# MCU.net
KiCad netlist of a schematic drawn in Altium Designer
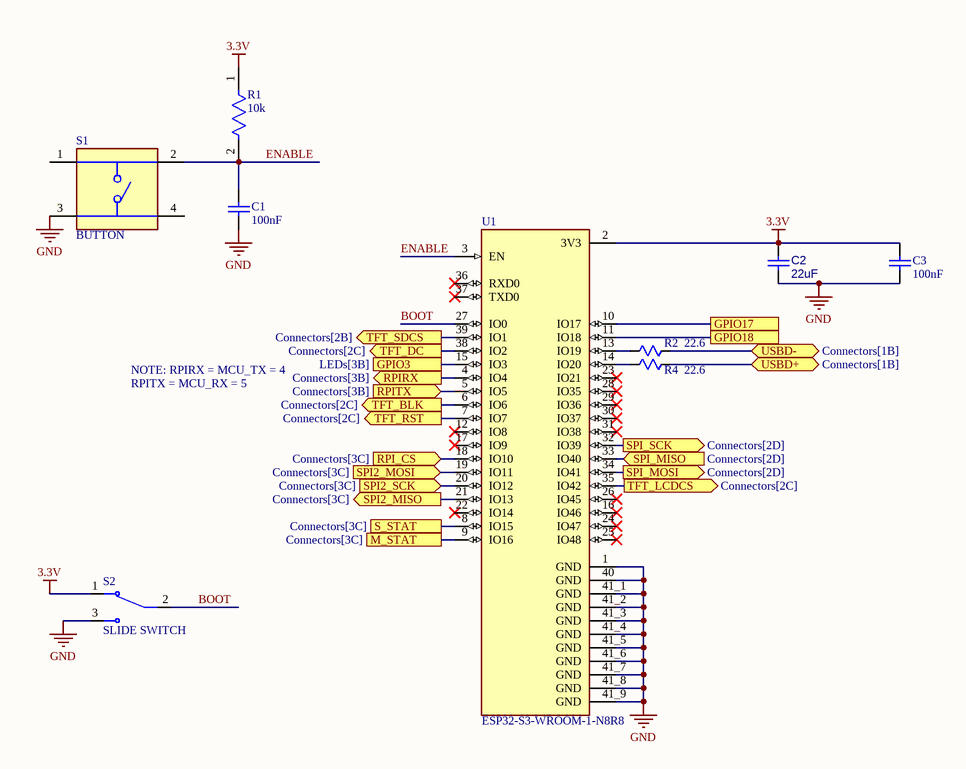
[diagram p0: MCU.SchDoc]

(export (version "E")
  (design (tool "Eeschema 10.0.6"))
  (components
    (comp (ref "C1")
      (value "100nF")
      (footprint "CAPC1608X90X35LL10T15")
      (fields (field (name "PART NUMBER") "GRM188R71E104KA01D") (field (name "MANUFACTURER") "Murata"))
      (libsource (lib "Altium Content Vault") (part "CAP"))
    )
    (comp (ref "C2")
      (value "22uF")
      (footprint "CAPC1608X09N")
      (description "CAP CER 22uF 10V X5R Symbols/Capacitor-Generic.SchLib")
      (fields (field (name "VOLTAGE") "10V") (field (name "PART NUMBER") "CAP-0603-000010"))
      (libsource (lib "Satellite Team") (part "CAP-NP-1"))
    )
    (comp (ref "C3")
      (value "100nF")
      (footprint "CAPC1608X90X35LL10T15")
      (fields (field (name "PART NUMBER") "GRM188R71E104KA01D") (field (name "MANUFACTURER") "Murata"))
      (libsource (lib "Altium Content Vault") (part "CAP"))
    )
    (comp (ref "R1")
      (value "10k")
      (footprint "FP-CRGP0603-IPC_C")
      (description "CRGP 0603 10K 1%")
      (fields
        (field (name "OCTOPART") "https://octopart.com/crgp0603f10k-te+connectivity-91018721")
        (field (name "MANUFACTURER PART NUMBER") "CRGP0603F10K")
      )
      (libsource (lib "Altium Content Vault") (part "1029c3af85768c4190bb7ad29bc67b5"))
    )
    (comp (ref "R2")
      (value "22.6")
      (footprint "RESC1608X06N")
      (description "RES 22.6 OHM 1% 1/10W 0603")
      (fields (field (name "PART NUMBER") "RES-0603-22R6-001") (field (name "TOLERANCE") "0.01%"))
      (libsource (lib "Satellite Team") (part "RES-1"))
    )
    (comp (ref "R4")
      (value "22.6")
      (footprint "RESC1608X06N")
      (description "RES 22.6 OHM 1% 1/10W 0603")
      (fields (field (name "PART NUMBER") "RES-0603-22R6-001") (field (name "TOLERANCE") "0.01%"))
      (libsource (lib "Satellite Team") (part "RES-1"))
    )
    (comp (ref "S1")
      (value "BUTTON")
      (footprint "SW_TS02-66-43-BK-100-SCR-D")
      (description "Switch Tactile OFF (ON) SPST Round Button PC Pins 0.05A 12VDC 100000Cycles 1N Thru-Hole Bag")
      (libsource (lib "Satellite Team") (part "TS02-66-43-BK-100-SCR-D"))
    )
    (comp (ref "S2")
      (value "SLIDE SWITCH")
      (footprint "SW_SLW-883935-2A-D")
      (description "Switch Slide ON ON SPDT Raised Slide 0.5A 30VDC 10000Cycles PC Pins Thru-Hole Box")
      (libsource (lib "Satellite Team") (part "SLW-883935-2A-D"))
    )
    (comp (ref "U1")
      (value "ESP32-S3-WROOM-1-N8R8")
      (footprint "XCVR_ESP32S3WROOM1N8R8")
      (description "Bluetooth, WiFi 802.11b/g/n, Bluetooth v5.0 Transceiver Module 2.4GHz PCB Trace Surface Mount")
      (fields (field (name "MF") "Espressif Systems"))
      (libsource (lib "ESP32-S3-WROOM-1-N8R8") (part "ESP32-S3-WROOM-1-N8R8"))
    )
  )
  (nets
    (net (code "1") (name "/BOOT") (class "Default")
      (node (ref "S2") (pin "2") (pinfunction "2_2") (pintype "passive"))
      (node (ref "U1") (pin "27") (pinfunction "IO0_27") (pintype "bidirectional"))
    )
    (net (code "2") (name "/ENABLE") (class "Default")
      (node (ref "C1") (pin "2") (pinfunction "2_2") (pintype "passive"))
      (node (ref "R1") (pin "2") (pinfunction "2_2") (pintype "passive"))
      (node (ref "S1") (pin "2") (pinfunction "2_2") (pintype "passive"))
      (node (ref "U1") (pin "3") (pinfunction "EN_3") (pintype "input"))
    )
    (net (code "3") (name "/GPIO3") (class "Default")
      (node (ref "U1") (pin "15") (pinfunction "IO3_15") (pintype "bidirectional"))
    )
    (net (code "4") (name "/GPIO17") (class "Default")
      (node (ref "U1") (pin "10") (pinfunction "IO17_10") (pintype "bidirectional"))
    )
    (net (code "5") (name "/GPIO18") (class "Default")
      (node (ref "U1") (pin "11") (pinfunction "IO18_11") (pintype "bidirectional"))
    )
    (net (code "6") (name "/M_STAT") (class "Default")
      (node (ref "U1") (pin "9") (pinfunction "IO16_9") (pintype "bidirectional"))
    )
    (net (code "7") (name "/RPIRX") (class "Default")
      (node (ref "U1") (pin "4") (pinfunction "IO4_4") (pintype "bidirectional"))
    )
    (net (code "8") (name "/RPITX") (class "Default")
      (node (ref "U1") (pin "5") (pinfunction "IO5_5") (pintype "bidirectional"))
    )
    (net (code "9") (name "/RPI_CS") (class "Default")
      (node (ref "U1") (pin "18") (pinfunction "IO10_18") (pintype "bidirectional"))
    )
    (net (code "10") (name "/SPI2_MISO") (class "Default")
      (node (ref "U1") (pin "21") (pinfunction "IO13_21") (pintype "bidirectional"))
    )
    (net (code "11") (name "/SPI2_MOSI") (class "Default")
      (node (ref "U1") (pin "19") (pinfunction "IO11_19") (pintype "bidirectional"))
    )
    (net (code "12") (name "/SPI2_SCK") (class "Default")
      (node (ref "U1") (pin "20") (pinfunction "IO12_20") (pintype "bidirectional"))
    )
    (net (code "13") (name "/SPI_MISO") (class "Default")
      (node (ref "U1") (pin "33") (pinfunction "IO40_33") (pintype "bidirectional"))
    )
    (net (code "14") (name "/SPI_MOSI") (class "Default")
      (node (ref "U1") (pin "34") (pinfunction "IO41_34") (pintype "bidirectional"))
    )
    (net (code "15") (name "/SPI_SCK") (class "Default")
      (node (ref "U1") (pin "32") (pinfunction "IO39_32") (pintype "bidirectional"))
    )
    (net (code "16") (name "/S_STAT") (class "Default")
      (node (ref "U1") (pin "8") (pinfunction "IO15_8") (pintype "bidirectional"))
    )
    (net (code "17") (name "/TFT_BLK") (class "Default")
      (node (ref "U1") (pin "6") (pinfunction "IO6_6") (pintype "bidirectional"))
    )
    (net (code "18") (name "/TFT_DC") (class "Default")
      (node (ref "U1") (pin "38") (pinfunction "IO2_38") (pintype "bidirectional"))
    )
    (net (code "19") (name "/TFT_LCDCS") (class "Default")
      (node (ref "U1") (pin "35") (pinfunction "IO42_35") (pintype "bidirectional"))
    )
    (net (code "20") (name "/TFT_RST") (class "Default")
      (node (ref "U1") (pin "7") (pinfunction "IO7_7") (pintype "bidirectional"))
    )
    (net (code "21") (name "/TFT_SDCS") (class "Default")
      (node (ref "U1") (pin "39") (pinfunction "IO1_39") (pintype "bidirectional"))
    )
    (net (code "22") (name "/USBD+") (class "Default")
      (node (ref "R4") (pin "2") (pinfunction "2_2") (pintype "passive"))
    )
    (net (code "23") (name "/USBD-") (class "Default")
      (node (ref "R2") (pin "2") (pinfunction "2_2") (pintype "passive"))
    )
    (net (code "24") (name "3.3V") (class "Default")
      (node (ref "C2") (pin "2") (pinfunction "2_2") (pintype "passive"))
      (node (ref "C3") (pin "2") (pinfunction "2_2") (pintype "passive"))
      (node (ref "R1") (pin "1") (pinfunction "1_1") (pintype "passive"))
      (node (ref "S2") (pin "1") (pinfunction "1_1") (pintype "passive"))
      (node (ref "U1") (pin "2") (pinfunction "3V3_2") (pintype "power_in"))
    )
    (net (code "25") (name "GND") (class "Default")
      (node (ref "C1") (pin "1") (pinfunction "1_1") (pintype "passive"))
      (node (ref "C2") (pin "1") (pinfunction "1_1") (pintype "passive"))
      (node (ref "C3") (pin "1") (pinfunction "1_1") (pintype "passive"))
      (node (ref "S1") (pin "3") (pinfunction "3_3") (pintype "passive"))
      (node (ref "S2") (pin "3") (pinfunction "3_3") (pintype "passive"))
      (node (ref "U1") (pin "1") (pinfunction "GND_1") (pintype "power_in"))
      (node (ref "U1") (pin "40") (pinfunction "GND_40") (pintype "power_in"))
      (node (ref "U1") (pin "41_1") (pinfunction "GND_41_1") (pintype "power_in"))
      (node (ref "U1") (pin "41_2") (pinfunction "GND_41_2") (pintype "power_in"))
      (node (ref "U1") (pin "41_3") (pinfunction "GND_41_3") (pintype "power_in"))
      (node (ref "U1") (pin "41_4") (pinfunction "GND_41_4") (pintype "power_in"))
      (node (ref "U1") (pin "41_5") (pinfunction "GND_41_5") (pintype "power_in"))
      (node (ref "U1") (pin "41_6") (pinfunction "GND_41_6") (pintype "power_in"))
      (node (ref "U1") (pin "41_7") (pinfunction "GND_41_7") (pintype "power_in"))
      (node (ref "U1") (pin "41_8") (pinfunction "GND_41_8") (pintype "power_in"))
      (node (ref "U1") (pin "41_9") (pinfunction "GND_41_9") (pintype "power_in"))
    )
    (net (code "26") (name "Net-(U1-IO19)") (class "Default")
      (node (ref "R2") (pin "1") (pinfunction "1_1") (pintype "passive"))
      (node (ref "U1") (pin "13") (pinfunction "IO19_13") (pintype "bidirectional"))
    )
    (net (code "27") (name "Net-(U1-IO20)") (class "Default")
      (node (ref "R4") (pin "1") (pinfunction "1_1") (pintype "passive"))
      (node (ref "U1") (pin "14") (pinfunction "IO20_14") (pintype "bidirectional"))
    )
    (net (code "28") (name "unconnected-(S1-Pad1)") (class "Default")
      (node (ref "S1") (pin "1") (pinfunction "1_1") (pintype "passive"))
    )
    (net (code "29") (name "unconnected-(S1-Pad4)") (class "Default")
      (node (ref "S1") (pin "4") (pinfunction "4_4") (pintype "passive"))
    )
    (net (code "30") (name "unconnected-(U1-IO8-Pad12)") (class "Default")
      (node (ref "U1") (pin "12") (pinfunction "IO8_12") (pintype "bidirectional+no_connect"))
    )
    (net (code "31") (name "unconnected-(U1-IO9-Pad17)") (class "Default")
      (node (ref "U1") (pin "17") (pinfunction "IO9_17") (pintype "bidirectional+no_connect"))
    )
    (net (code "32") (name "unconnected-(U1-IO14-Pad22)") (class "Default")
      (node (ref "U1") (pin "22") (pinfunction "IO14_22") (pintype "bidirectional+no_connect"))
    )
    (net (code "33") (name "unconnected-(U1-IO21-Pad23)") (class "Default")
      (node (ref "U1") (pin "23") (pinfunction "IO21_23") (pintype "bidirectional+no_connect"))
    )
    (net (code "34") (name "unconnected-(U1-IO35-Pad28)") (class "Default")
      (node (ref "U1") (pin "28") (pinfunction "IO35_28") (pintype "bidirectional+no_connect"))
    )
    (net (code "35") (name "unconnected-(U1-IO36-Pad29)") (class "Default")
      (node (ref "U1") (pin "29") (pinfunction "IO36_29") (pintype "bidirectional+no_connect"))
    )
    (net (code "36") (name "unconnected-(U1-IO37-Pad30)") (class "Default")
      (node (ref "U1") (pin "30") (pinfunction "IO37_30") (pintype "bidirectional+no_connect"))
    )
    (net (code "37") (name "unconnected-(U1-IO38-Pad31)") (class "Default")
      (node (ref "U1") (pin "31") (pinfunction "IO38_31") (pintype "bidirectional+no_connect"))
    )
    (net (code "38") (name "unconnected-(U1-IO45-Pad26)") (class "Default")
      (node (ref "U1") (pin "26") (pinfunction "IO45_26") (pintype "bidirectional+no_connect"))
    )
    (net (code "39") (name "unconnected-(U1-IO46-Pad16)") (class "Default")
      (node (ref "U1") (pin "16") (pinfunction "IO46_16") (pintype "bidirectional+no_connect"))
    )
    (net (code "40") (name "unconnected-(U1-IO47-Pad24)") (class "Default")
      (node (ref "U1") (pin "24") (pinfunction "IO47_24") (pintype "bidirectional+no_connect"))
    )
    (net (code "41") (name "unconnected-(U1-IO48-Pad25)") (class "Default")
      (node (ref "U1") (pin "25") (pinfunction "IO48_25") (pintype "bidirectional+no_connect"))
    )
    (net (code "42") (name "unconnected-(U1-RXD0-Pad36)") (class "Default")
      (node (ref "U1") (pin "36") (pinfunction "RXD0_36") (pintype "bidirectional+no_connect"))
    )
    (net (code "43") (name "unconnected-(U1-TXD0-Pad37)") (class "Default")
      (node (ref "U1") (pin "37") (pinfunction "TXD0_37") (pintype "bidirectional+no_connect"))
    )
  )
)
